# buffNlvlshifter.net
KiCad netlist of a schematic drawn in Altium Designer
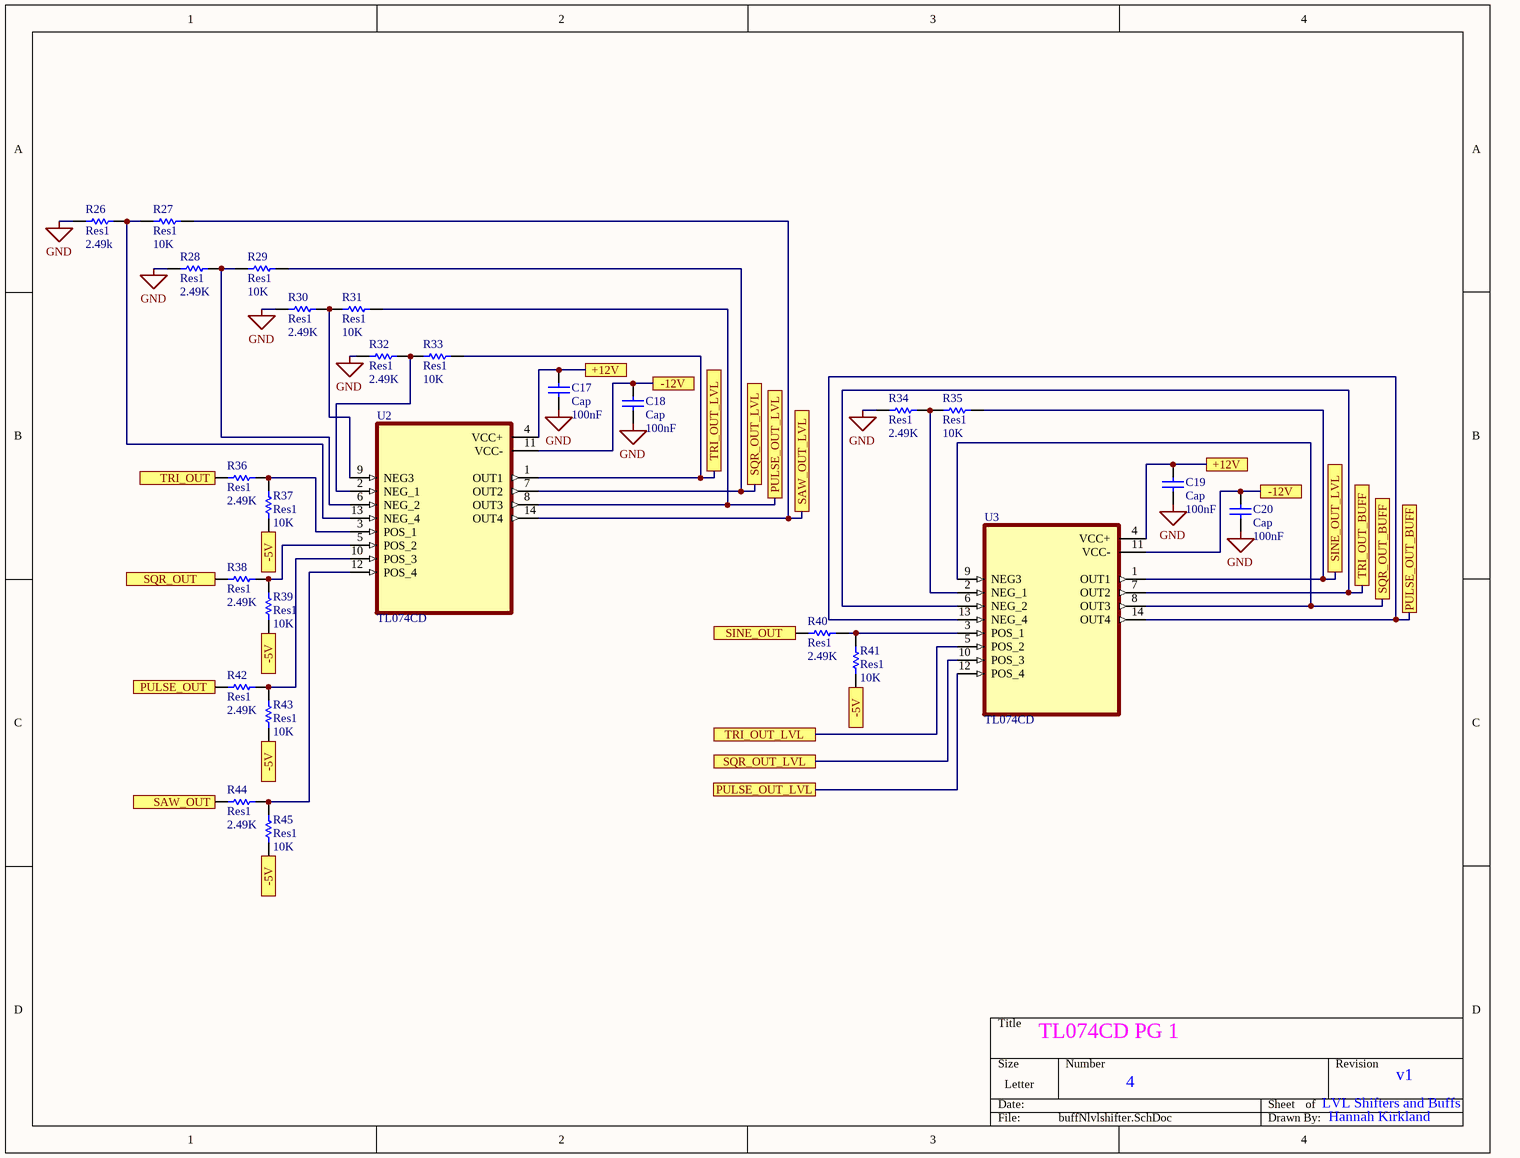
[diagram p0: buffNlvlshifter.SchDoc]

(export (version "E")
  (design (tool "Eeschema 10.0.6"))
  (components
    (comp (ref "C17")
      (value "Cap")
      (footprint "C1206")
      (description "Capacitor")
      (fields (field (name "ALTIUM_VALUE") "100nF") (field (name "PUBLISHER") "Altium Limited"))
      (libsource (lib "Miscellaneous Devices") (part "Cap"))
    )
    (comp (ref "C18")
      (value "Cap")
      (footprint "C1206")
      (description "Capacitor")
      (fields (field (name "ALTIUM_VALUE") "100nF") (field (name "PUBLISHER") "Altium Limited"))
      (libsource (lib "Miscellaneous Devices") (part "Cap"))
    )
    (comp (ref "C19")
      (value "Cap")
      (footprint "C1206")
      (description "Capacitor")
      (fields (field (name "ALTIUM_VALUE") "100nF") (field (name "PUBLISHER") "Altium Limited"))
      (libsource (lib "Miscellaneous Devices") (part "Cap"))
    )
    (comp (ref "C20")
      (value "Cap")
      (footprint "C1206")
      (description "Capacitor")
      (fields (field (name "ALTIUM_VALUE") "100nF") (field (name "PUBLISHER") "Altium Limited"))
      (libsource (lib "Miscellaneous Devices") (part "Cap"))
    )
    (comp (ref "R26")
      (value "Res1")
      (footprint "C1206")
      (description "Resistor")
      (fields (field (name "ALTIUM_VALUE") "2.49k") (field (name "PUBLISHER") "Altium Limited"))
      (libsource (lib "Miscellaneous Devices") (part "Res1"))
    )
    (comp (ref "R27")
      (value "Res1")
      (footprint "C1206")
      (description "Resistor")
      (fields (field (name "ALTIUM_VALUE") "10K") (field (name "PUBLISHER") "Altium Limited"))
      (libsource (lib "Miscellaneous Devices") (part "Res1"))
    )
    (comp (ref "R28")
      (value "Res1")
      (footprint "C1206")
      (description "Resistor")
      (fields (field (name "ALTIUM_VALUE") "2.49K") (field (name "PUBLISHER") "Altium Limited"))
      (libsource (lib "Miscellaneous Devices") (part "Res1"))
    )
    (comp (ref "R29")
      (value "Res1")
      (footprint "C1206")
      (description "Resistor")
      (fields (field (name "ALTIUM_VALUE") "10K") (field (name "PUBLISHER") "Altium Limited"))
      (libsource (lib "Miscellaneous Devices") (part "Res1"))
    )
    (comp (ref "R30")
      (value "Res1")
      (footprint "C1206")
      (description "Resistor")
      (fields (field (name "ALTIUM_VALUE") "2.49K") (field (name "PUBLISHER") "Altium Limited"))
      (libsource (lib "Miscellaneous Devices") (part "Res1"))
    )
    (comp (ref "R31")
      (value "Res1")
      (footprint "C1206")
      (description "Resistor")
      (fields (field (name "ALTIUM_VALUE") "10K") (field (name "PUBLISHER") "Altium Limited"))
      (libsource (lib "Miscellaneous Devices") (part "Res1"))
    )
    (comp (ref "R32")
      (value "Res1")
      (footprint "C1206")
      (description "Resistor")
      (fields (field (name "ALTIUM_VALUE") "2.49K") (field (name "PUBLISHER") "Altium Limited"))
      (libsource (lib "Miscellaneous Devices") (part "Res1"))
    )
    (comp (ref "R33")
      (value "Res1")
      (footprint "C1206")
      (description "Resistor")
      (fields (field (name "ALTIUM_VALUE") "10K") (field (name "PUBLISHER") "Altium Limited"))
      (libsource (lib "Miscellaneous Devices") (part "Res1"))
    )
    (comp (ref "R34")
      (value "Res1")
      (footprint "C1206")
      (description "Resistor")
      (fields (field (name "ALTIUM_VALUE") "2.49K") (field (name "PUBLISHER") "Altium Limited"))
      (libsource (lib "Miscellaneous Devices") (part "Res1"))
    )
    (comp (ref "R35")
      (value "Res1")
      (footprint "C1206")
      (description "Resistor")
      (fields (field (name "ALTIUM_VALUE") "10K") (field (name "PUBLISHER") "Altium Limited"))
      (libsource (lib "Miscellaneous Devices") (part "Res1"))
    )
    (comp (ref "R36")
      (value "Res1")
      (footprint "C1206")
      (description "Resistor")
      (fields (field (name "ALTIUM_VALUE") "2.49K") (field (name "PUBLISHER") "Altium Limited"))
      (libsource (lib "Miscellaneous Devices") (part "Res1"))
    )
    (comp (ref "R37")
      (value "Res1")
      (footprint "C1206")
      (description "Resistor")
      (fields (field (name "ALTIUM_VALUE") "10K") (field (name "PUBLISHER") "Altium Limited"))
      (libsource (lib "Miscellaneous Devices") (part "Res1"))
    )
    (comp (ref "R38")
      (value "Res1")
      (footprint "C1206")
      (description "Resistor")
      (fields (field (name "ALTIUM_VALUE") "2.49K") (field (name "PUBLISHER") "Altium Limited"))
      (libsource (lib "Miscellaneous Devices") (part "Res1"))
    )
    (comp (ref "R39")
      (value "Res1")
      (footprint "C1206")
      (description "Resistor")
      (fields (field (name "ALTIUM_VALUE") "10K") (field (name "PUBLISHER") "Altium Limited"))
      (libsource (lib "Miscellaneous Devices") (part "Res1"))
    )
    (comp (ref "R40")
      (value "Res1")
      (footprint "C1206")
      (description "Resistor")
      (fields (field (name "ALTIUM_VALUE") "2.49K") (field (name "PUBLISHER") "Altium Limited"))
      (libsource (lib "Miscellaneous Devices") (part "Res1"))
    )
    (comp (ref "R41")
      (value "Res1")
      (footprint "C1206")
      (description "Resistor")
      (fields (field (name "ALTIUM_VALUE") "10K") (field (name "PUBLISHER") "Altium Limited"))
      (libsource (lib "Miscellaneous Devices") (part "Res1"))
    )
    (comp (ref "R42")
      (value "Res1")
      (footprint "C1206")
      (description "Resistor")
      (fields (field (name "ALTIUM_VALUE") "2.49K") (field (name "PUBLISHER") "Altium Limited"))
      (libsource (lib "Miscellaneous Devices") (part "Res1"))
    )
    (comp (ref "R43")
      (value "Res1")
      (footprint "C1206")
      (description "Resistor")
      (fields (field (name "ALTIUM_VALUE") "10K") (field (name "PUBLISHER") "Altium Limited"))
      (libsource (lib "Miscellaneous Devices") (part "Res1"))
    )
    (comp (ref "R44")
      (value "Res1")
      (footprint "C1206")
      (description "Resistor")
      (fields (field (name "ALTIUM_VALUE") "2.49K") (field (name "PUBLISHER") "Altium Limited"))
      (libsource (lib "Miscellaneous Devices") (part "Res1"))
    )
    (comp (ref "R45")
      (value "Res1")
      (footprint "C1206")
      (description "Resistor")
      (fields (field (name "ALTIUM_VALUE") "10K") (field (name "PUBLISHER") "Altium Limited"))
      (libsource (lib "Miscellaneous Devices") (part "Res1"))
    )
    (comp (ref "U2")
      (value "TL074CD")
      (footprint "SOIC127P600X175-14N")
      (description "Quad Low-Noise JFET-Input General-Purpose Operational Amplifier 14-SOIC 0 to 70")
      (fields
        (field (name "MF") "Texas Instruments")
        (field (name "BUYPART") "https://www.snapeda.com/parts/TL074CD/Texas%20Instruments/view-part/4793449/?ref=eda")
      )
      (libsource (lib "TL074CD") (part "TL074CD"))
    )
    (comp (ref "U3")
      (value "TL074CD")
      (footprint "SOIC127P600X175-14N")
      (description "Quad Low-Noise JFET-Input General-Purpose Operational Amplifier 14-SOIC 0 to 70")
      (fields
        (field (name "MF") "Texas Instruments")
        (field (name "BUYPART") "https://www.snapeda.com/parts/TL074CD/Texas%20Instruments/view-part/4793449/?ref=eda")
      )
      (libsource (lib "TL074CD") (part "TL074CD"))
    )
  )
  (nets
    (net (code "1") (name "/+12V") (class "Default")
      (node (ref "C17") (pin "2") (pinfunction "2_2") (pintype "passive"))
      (node (ref "C19") (pin "2") (pinfunction "2_2") (pintype "passive"))
      (node (ref "U2") (pin "4") (pinfunction "VCC+_4") (pintype "power_in"))
      (node (ref "U3") (pin "4") (pinfunction "VCC+_4") (pintype "power_in"))
    )
    (net (code "2") (name "/-5V") (class "Default")
      (node (ref "R37") (pin "1") (pinfunction "1_1") (pintype "passive"))
      (node (ref "R39") (pin "1") (pinfunction "1_1") (pintype "passive"))
      (node (ref "R41") (pin "1") (pinfunction "1_1") (pintype "passive"))
      (node (ref "R43") (pin "1") (pinfunction "1_1") (pintype "passive"))
      (node (ref "R45") (pin "1") (pinfunction "1_1") (pintype "passive"))
    )
    (net (code "3") (name "/-12V") (class "Default")
      (node (ref "C18") (pin "2") (pinfunction "2_2") (pintype "passive"))
      (node (ref "C20") (pin "2") (pinfunction "2_2") (pintype "passive"))
      (node (ref "U2") (pin "11") (pinfunction "VCC-_11") (pintype "power_in"))
      (node (ref "U3") (pin "11") (pinfunction "VCC-_11") (pintype "power_in"))
    )
    (net (code "4") (name "/PULSE_OUT") (class "Default")
      (node (ref "R42") (pin "1") (pinfunction "1_1") (pintype "passive"))
    )
    (net (code "5") (name "/PULSE_OUT_BUFF") (class "Default")
      (node (ref "U3") (pin "13") (pinfunction "NEG_4_13") (pintype "input"))
      (node (ref "U3") (pin "14") (pinfunction "OUT4_14") (pintype "output"))
    )
    (net (code "6") (name "/PULSE_OUT_LVL") (class "Default")
      (node (ref "R31") (pin "2") (pinfunction "2_2") (pintype "passive"))
      (node (ref "U2") (pin "8") (pinfunction "OUT3_8") (pintype "output"))
      (node (ref "U3") (pin "12") (pinfunction "POS_4_12") (pintype "input"))
    )
    (net (code "7") (name "/SAW_OUT") (class "Default")
      (node (ref "R44") (pin "1") (pinfunction "1_1") (pintype "passive"))
    )
    (net (code "8") (name "/SAW_OUT_LVL") (class "Default")
      (node (ref "R27") (pin "2") (pinfunction "2_2") (pintype "passive"))
      (node (ref "U2") (pin "14") (pinfunction "OUT4_14") (pintype "output"))
    )
    (net (code "9") (name "/SINE_OUT") (class "Default")
      (node (ref "R40") (pin "1") (pinfunction "1_1") (pintype "passive"))
    )
    (net (code "10") (name "/SINE_OUT_LVL") (class "Default")
      (node (ref "R35") (pin "2") (pinfunction "2_2") (pintype "passive"))
      (node (ref "U3") (pin "1") (pinfunction "OUT1_1") (pintype "output"))
    )
    (net (code "11") (name "/SQR_OUT") (class "Default")
      (node (ref "R38") (pin "1") (pinfunction "1_1") (pintype "passive"))
    )
    (net (code "12") (name "/SQR_OUT_BUFF") (class "Default")
      (node (ref "U3") (pin "8") (pinfunction "OUT3_8") (pintype "output"))
      (node (ref "U3") (pin "9") (pinfunction "NEG3_9") (pintype "input"))
    )
    (net (code "13") (name "/SQR_OUT_LVL") (class "Default")
      (node (ref "R29") (pin "2") (pinfunction "2_2") (pintype "passive"))
      (node (ref "U2") (pin "7") (pinfunction "OUT2_7") (pintype "output"))
      (node (ref "U3") (pin "10") (pinfunction "POS_3_10") (pintype "input"))
    )
    (net (code "14") (name "/TRI_OUT") (class "Default")
      (node (ref "R36") (pin "1") (pinfunction "1_1") (pintype "passive"))
    )
    (net (code "15") (name "/TRI_OUT_BUFF") (class "Default")
      (node (ref "U3") (pin "6") (pinfunction "NEG_2_6") (pintype "input"))
      (node (ref "U3") (pin "7") (pinfunction "OUT2_7") (pintype "output"))
    )
    (net (code "16") (name "/TRI_OUT_LVL") (class "Default")
      (node (ref "R33") (pin "2") (pinfunction "2_2") (pintype "passive"))
      (node (ref "U2") (pin "1") (pinfunction "OUT1_1") (pintype "output"))
      (node (ref "U3") (pin "5") (pinfunction "POS_2_5") (pintype "input"))
    )
    (net (code "17") (name "GND") (class "Default")
      (node (ref "C17") (pin "1") (pinfunction "1_1") (pintype "passive"))
      (node (ref "C18") (pin "1") (pinfunction "1_1") (pintype "passive"))
      (node (ref "C19") (pin "1") (pinfunction "1_1") (pintype "passive"))
      (node (ref "C20") (pin "1") (pinfunction "1_1") (pintype "passive"))
      (node (ref "R26") (pin "1") (pinfunction "1_1") (pintype "passive"))
      (node (ref "R28") (pin "1") (pinfunction "1_1") (pintype "passive"))
      (node (ref "R30") (pin "1") (pinfunction "1_1") (pintype "passive"))
      (node (ref "R32") (pin "1") (pinfunction "1_1") (pintype "passive"))
      (node (ref "R34") (pin "1") (pinfunction "1_1") (pintype "passive"))
    )
    (net (code "18") (name "Net-(U2-NEG3)") (class "Default")
      (node (ref "R30") (pin "2") (pinfunction "2_2") (pintype "passive"))
      (node (ref "R31") (pin "1") (pinfunction "1_1") (pintype "passive"))
      (node (ref "U2") (pin "9") (pinfunction "NEG3_9") (pintype "input"))
    )
    (net (code "19") (name "Net-(U2-NEG_1)") (class "Default")
      (node (ref "R32") (pin "2") (pinfunction "2_2") (pintype "passive"))
      (node (ref "R33") (pin "1") (pinfunction "1_1") (pintype "passive"))
      (node (ref "U2") (pin "2") (pinfunction "NEG_1_2") (pintype "input"))
    )
    (net (code "20") (name "Net-(U2-NEG_2)") (class "Default")
      (node (ref "R28") (pin "2") (pinfunction "2_2") (pintype "passive"))
      (node (ref "R29") (pin "1") (pinfunction "1_1") (pintype "passive"))
      (node (ref "U2") (pin "6") (pinfunction "NEG_2_6") (pintype "input"))
    )
    (net (code "21") (name "Net-(U2-NEG_4)") (class "Default")
      (node (ref "R26") (pin "2") (pinfunction "2_2") (pintype "passive"))
      (node (ref "R27") (pin "1") (pinfunction "1_1") (pintype "passive"))
      (node (ref "U2") (pin "13") (pinfunction "NEG_4_13") (pintype "input"))
    )
    (net (code "22") (name "Net-(U2-POS_1)") (class "Default")
      (node (ref "R36") (pin "2") (pinfunction "2_2") (pintype "passive"))
      (node (ref "R37") (pin "2") (pinfunction "2_2") (pintype "passive"))
      (node (ref "U2") (pin "3") (pinfunction "POS_1_3") (pintype "input"))
    )
    (net (code "23") (name "Net-(U2-POS_2)") (class "Default")
      (node (ref "R38") (pin "2") (pinfunction "2_2") (pintype "passive"))
      (node (ref "R39") (pin "2") (pinfunction "2_2") (pintype "passive"))
      (node (ref "U2") (pin "5") (pinfunction "POS_2_5") (pintype "input"))
    )
    (net (code "24") (name "Net-(U2-POS_3)") (class "Default")
      (node (ref "R42") (pin "2") (pinfunction "2_2") (pintype "passive"))
      (node (ref "R43") (pin "2") (pinfunction "2_2") (pintype "passive"))
      (node (ref "U2") (pin "10") (pinfunction "POS_3_10") (pintype "input"))
    )
    (net (code "25") (name "Net-(U2-POS_4)") (class "Default")
      (node (ref "R44") (pin "2") (pinfunction "2_2") (pintype "passive"))
      (node (ref "R45") (pin "2") (pinfunction "2_2") (pintype "passive"))
      (node (ref "U2") (pin "12") (pinfunction "POS_4_12") (pintype "input"))
    )
    (net (code "26") (name "Net-(U3-NEG_1)") (class "Default")
      (node (ref "R34") (pin "2") (pinfunction "2_2") (pintype "passive"))
      (node (ref "R35") (pin "1") (pinfunction "1_1") (pintype "passive"))
      (node (ref "U3") (pin "2") (pinfunction "NEG_1_2") (pintype "input"))
    )
    (net (code "27") (name "Net-(U3-POS_1)") (class "Default")
      (node (ref "R40") (pin "2") (pinfunction "2_2") (pintype "passive"))
      (node (ref "R41") (pin "2") (pinfunction "2_2") (pintype "passive"))
      (node (ref "U3") (pin "3") (pinfunction "POS_1_3") (pintype "input"))
    )
  )
)
